# PressureSensor.net
KiCad netlist of a schematic drawn in Altium Designer
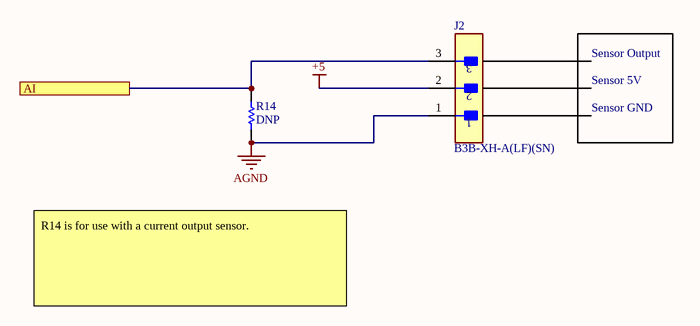
[diagram p0: PressureSensor.SchDoc]

(export (version "E")
  (design (tool "Eeschema 10.0.6"))
  (components
    (comp (ref "J2")
      (value "B3B-XH-A(LF)(SN)")
      (footprint "FP-B3B-XH-A_LF_SN-MFG")
      (description "CONN HEADER VERT 3POS 2.5MM")
      (fields
        (field (name "OCTOPART") "https://octopart.com/b3b-xh-a%28lf%29%28sn%29-jst-3990185")
        (field (name "MANUFACTURER") "JST")
      )
      (libsource (lib "Altium Content Vault") (part "0d3f023dd272f625e17a2be33dea85f"))
    )
    (comp (ref "R14")
      (value "DNP")
      (footprint "RESC0603(1608)_L")
      (description "249R 0.1W 1% 0603 (1608 Metric)  SMD")
      (fields (field (name "TOLERANCE") "1 %") (field (name "POWER") "0.1 W"))
      (libsource (lib "Altium Content Vault") (part "RES"))
    )
  )
  (nets
    (net (code "1") (name "+5") (class "Default")
      (node (ref "J2") (pin "2") (pinfunction "2_2") (pintype "passive"))
    )
    (net (code "2") (name "/AI") (class "Default")
      (node (ref "J2") (pin "3") (pinfunction "3_3") (pintype "passive"))
      (node (ref "R14") (pin "1") (pinfunction "1_1") (pintype "passive"))
    )
    (net (code "3") (name "AGND") (class "Default")
      (node (ref "J2") (pin "1") (pinfunction "1_1") (pintype "passive"))
      (node (ref "R14") (pin "2") (pinfunction "2_2") (pintype "passive"))
    )
  )
)
